# nola2.net
KiCad netlist of a schematic drawn in EAGLE
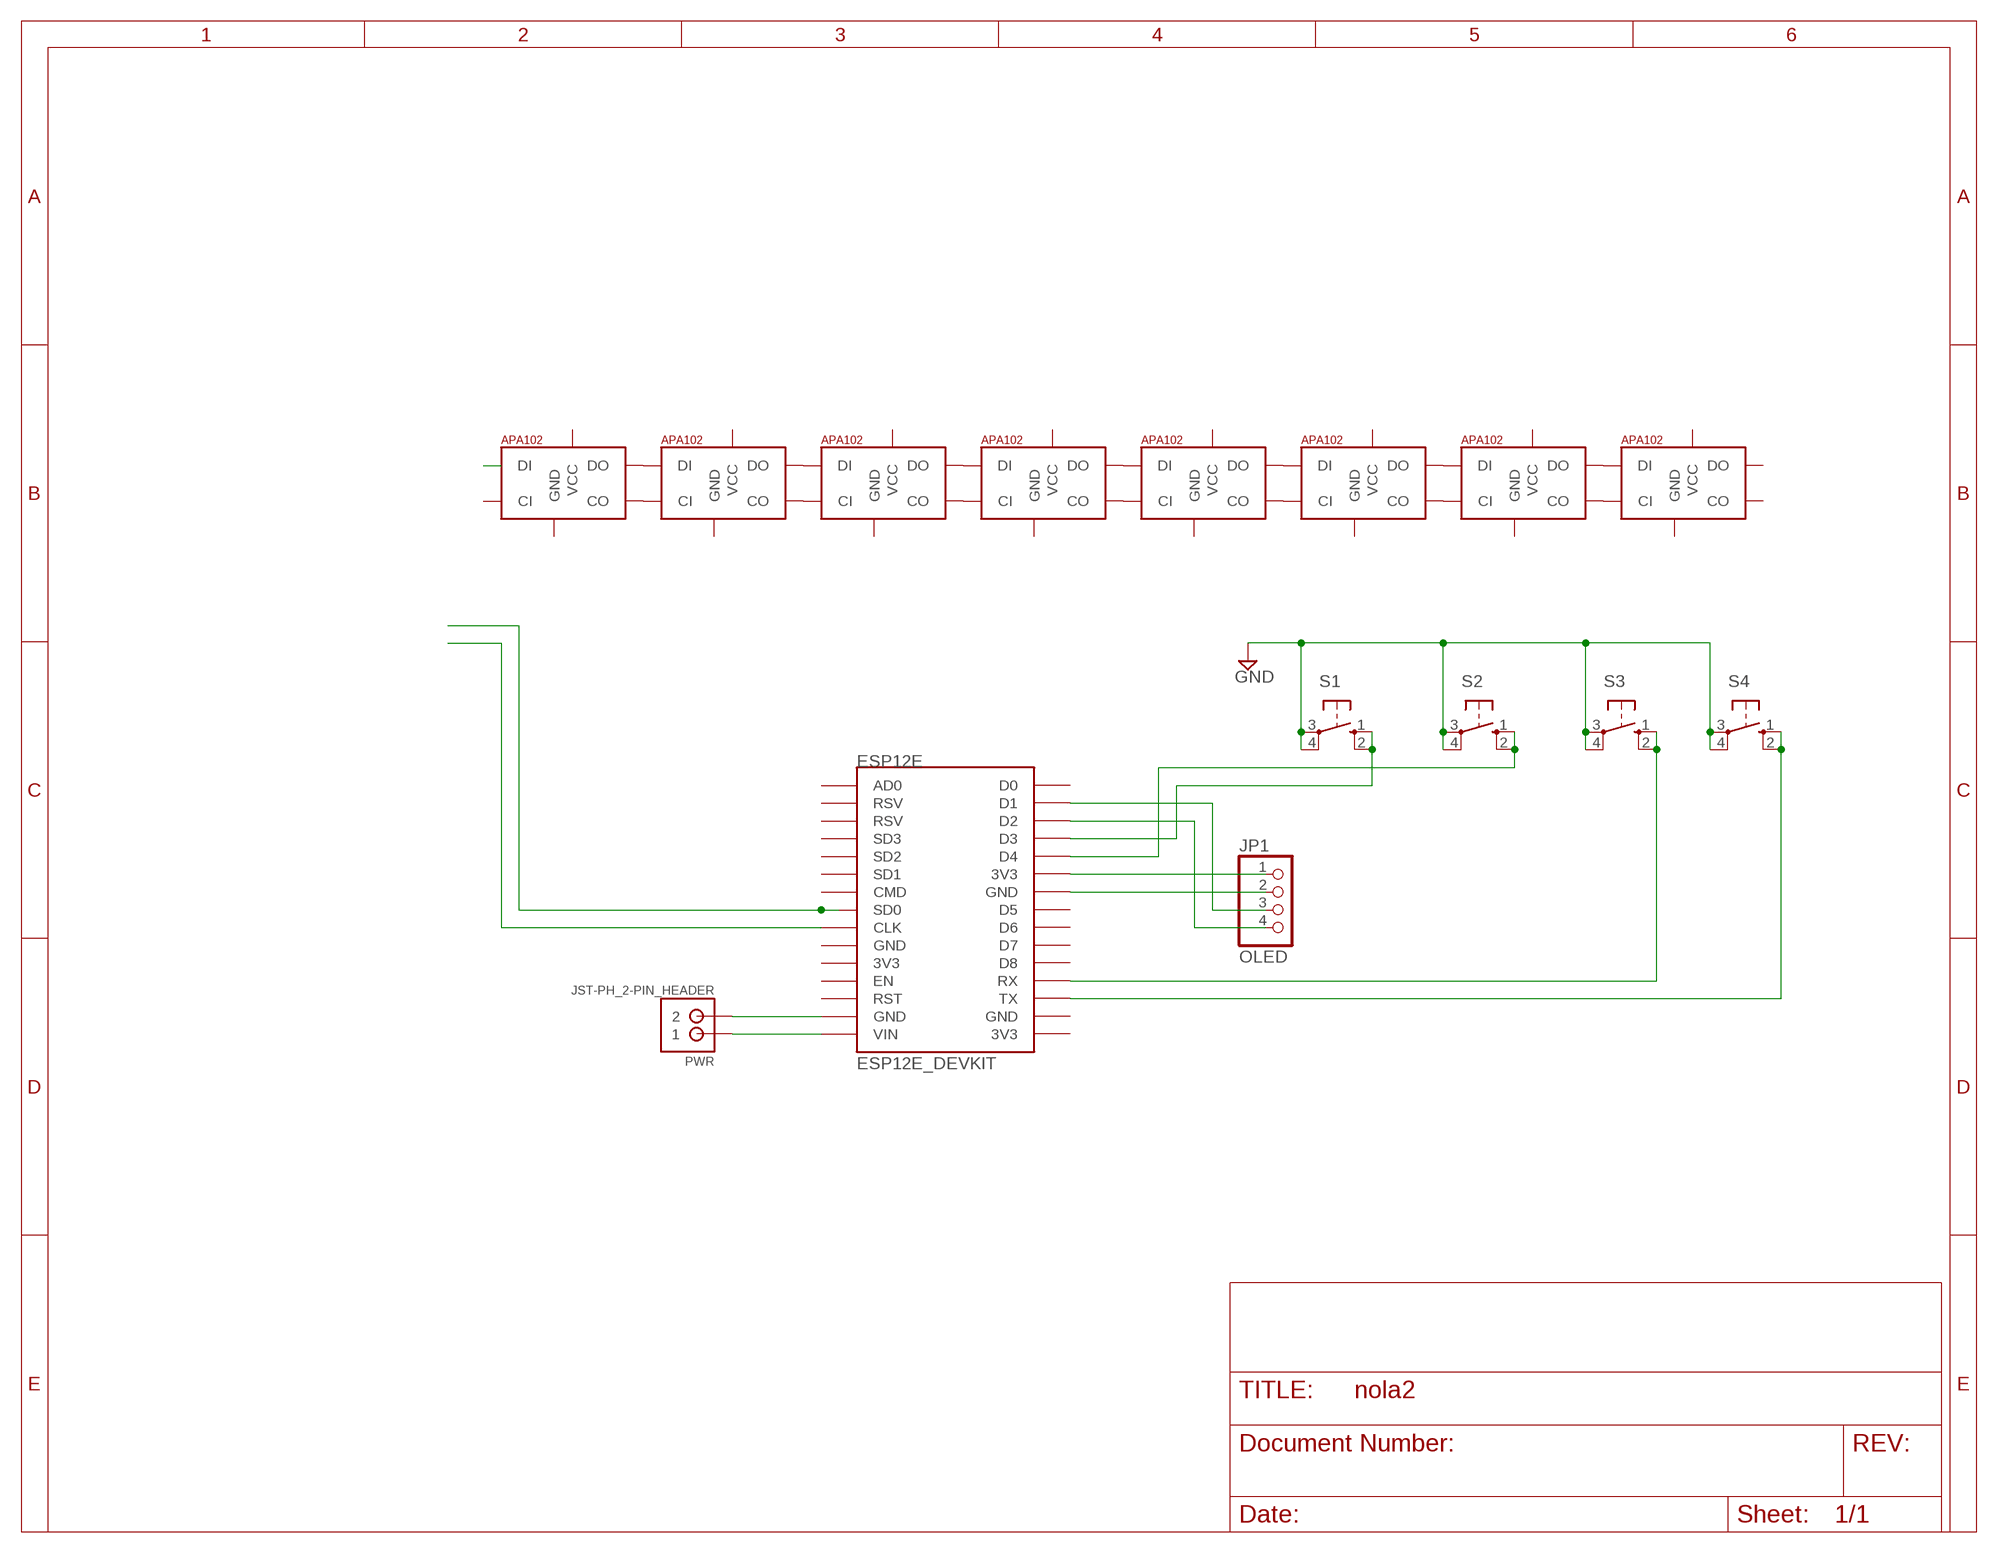
[diagram p0: schematic, sheet 1]

(export (version "E")
  (design (tool "Eeschema 10.0.6"))
  (components
    (comp (ref "ESP12E")
      (value "ESP12E_DEVKIT")
      (footprint "eagle-import:ESP12E_DEVKIT")
      (libsource (lib "eagle-import") (part "ESP12E_DEVKIT"))
    )
    (comp (ref "JP1")
      (value "OLED")
      (footprint "eagle-import:1X04")
      (libsource (lib "eagle-import") (part "PINHD-1X4"))
    )
    (comp (ref "LED1")
      (value "APA1025050")
      (footprint "eagle-import:APA102_5050")
      (libsource (lib "eagle-import") (part "APA1025050"))
    )
    (comp (ref "LED2")
      (value "APA1025050")
      (footprint "eagle-import:APA102_5050")
      (libsource (lib "eagle-import") (part "APA1025050"))
    )
    (comp (ref "LED3")
      (value "APA1025050")
      (footprint "eagle-import:APA102_5050")
      (libsource (lib "eagle-import") (part "APA1025050"))
    )
    (comp (ref "LED4")
      (value "APA1025050")
      (footprint "eagle-import:APA102_5050")
      (libsource (lib "eagle-import") (part "APA1025050"))
    )
    (comp (ref "LED5")
      (value "APA1025050")
      (footprint "eagle-import:APA102_5050")
      (libsource (lib "eagle-import") (part "APA1025050"))
    )
    (comp (ref "LED6")
      (value "APA1025050")
      (footprint "eagle-import:APA102_5050")
      (libsource (lib "eagle-import") (part "APA1025050"))
    )
    (comp (ref "LED7")
      (value "APA1025050")
      (footprint "eagle-import:APA102_5050")
      (libsource (lib "eagle-import") (part "APA1025050"))
    )
    (comp (ref "LED8")
      (value "APA1025050")
      (footprint "eagle-import:APA102_5050")
      (libsource (lib "eagle-import") (part "APA1025050"))
    )
    (comp (ref "PWR")
      (value "JST-PH_2-PIN_HEADER")
      (footprint "eagle-import:JST_B2B-PH_HEADER")
      (libsource (lib "eagle-import") (part "JST-PH_2-PIN_HEADER"))
    )
    (comp (ref "S1")
      (value "10-XX")
      (footprint "eagle-import:B3F-10XX")
      (fields (field (name "MPN") "B3F-1000"))
      (libsource (lib "eagle-import") (part "10-XX"))
    )
    (comp (ref "S2")
      (value "10-XX")
      (footprint "eagle-import:B3F-10XX")
      (fields (field (name "MPN") "B3F-1000"))
      (libsource (lib "eagle-import") (part "10-XX"))
    )
    (comp (ref "S3")
      (value "10-XX")
      (footprint "eagle-import:B3F-10XX")
      (fields (field (name "MPN") "B3F-1000"))
      (libsource (lib "eagle-import") (part "10-XX"))
    )
    (comp (ref "S4")
      (value "10-XX")
      (footprint "eagle-import:B3F-10XX")
      (fields (field (name "MPN") "B3F-1000"))
      (libsource (lib "eagle-import") (part "10-XX"))
    )
  )
  (nets
    (net (code "1") (name "GND") (class "Default")
      (node (ref "S1") (pin "3") (pinfunction "P_3") (pintype "passive"))
      (node (ref "S1") (pin "4") (pinfunction "P1_4") (pintype "passive"))
      (node (ref "S2") (pin "3") (pinfunction "P_3") (pintype "passive"))
      (node (ref "S2") (pin "4") (pinfunction "P1_4") (pintype "passive"))
      (node (ref "S3") (pin "3") (pinfunction "P_3") (pintype "passive"))
      (node (ref "S3") (pin "4") (pinfunction "P1_4") (pintype "passive"))
      (node (ref "S4") (pin "3") (pinfunction "P_3") (pintype "passive"))
      (node (ref "S4") (pin "4") (pinfunction "P1_4") (pintype "passive"))
    )
    (net (code "2") (name "Net-(ESP12E-3V3-Pad3V3@1)") (class "Default")
      (node (ref "ESP12E") (pin "3V3@1") (pinfunction "3V3_3V3@1") (pintype "bidirectional"))
      (node (ref "JP1") (pin "1") (pinfunction "1_1") (pintype "passive"))
    )
    (net (code "3") (name "Net-(ESP12E-GND-PadGND@2)") (class "Default")
      (node (ref "ESP12E") (pin "GND@2") (pinfunction "GND_GND@2") (pintype "bidirectional"))
      (node (ref "JP1") (pin "2") (pinfunction "2_2") (pintype "passive"))
    )
    (net (code "4") (name "Net-(ESP12E-PadD1)") (class "Default")
      (node (ref "ESP12E") (pin "D1") (pinfunction "D1_D1") (pintype "bidirectional"))
      (node (ref "JP1") (pin "3") (pinfunction "3_3") (pintype "passive"))
    )
    (net (code "5") (name "Net-(ESP12E-PadD2)") (class "Default")
      (node (ref "ESP12E") (pin "D2") (pinfunction "D2_D2") (pintype "bidirectional"))
      (node (ref "JP1") (pin "4") (pinfunction "4_4") (pintype "passive"))
    )
    (net (code "6") (name "Net-(LED1-CO)") (class "Default")
      (node (ref "LED1") (pin "2") (pinfunction "CO_2") (pintype "bidirectional"))
      (node (ref "LED2") (pin "5") (pinfunction "CI_5") (pintype "bidirectional"))
    )
    (net (code "7") (name "Net-(LED1-DO)") (class "Default")
      (node (ref "LED1") (pin "3") (pinfunction "DO_3") (pintype "bidirectional"))
      (node (ref "LED2") (pin "4") (pinfunction "DI_4") (pintype "bidirectional"))
    )
    (net (code "8") (name "Net-(LED2-CO)") (class "Default")
      (node (ref "LED2") (pin "2") (pinfunction "CO_2") (pintype "bidirectional"))
      (node (ref "LED3") (pin "5") (pinfunction "CI_5") (pintype "bidirectional"))
    )
    (net (code "9") (name "Net-(LED2-DO)") (class "Default")
      (node (ref "LED2") (pin "3") (pinfunction "DO_3") (pintype "bidirectional"))
      (node (ref "LED3") (pin "4") (pinfunction "DI_4") (pintype "bidirectional"))
    )
    (net (code "10") (name "Net-(LED3-CO)") (class "Default")
      (node (ref "LED3") (pin "2") (pinfunction "CO_2") (pintype "bidirectional"))
      (node (ref "LED4") (pin "5") (pinfunction "CI_5") (pintype "bidirectional"))
    )
    (net (code "11") (name "Net-(LED3-DO)") (class "Default")
      (node (ref "LED3") (pin "3") (pinfunction "DO_3") (pintype "bidirectional"))
      (node (ref "LED4") (pin "4") (pinfunction "DI_4") (pintype "bidirectional"))
    )
    (net (code "12") (name "Net-(LED4-CO)") (class "Default")
      (node (ref "LED4") (pin "2") (pinfunction "CO_2") (pintype "bidirectional"))
      (node (ref "LED5") (pin "5") (pinfunction "CI_5") (pintype "bidirectional"))
    )
    (net (code "13") (name "Net-(LED4-DO)") (class "Default")
      (node (ref "LED4") (pin "3") (pinfunction "DO_3") (pintype "bidirectional"))
      (node (ref "LED5") (pin "4") (pinfunction "DI_4") (pintype "bidirectional"))
    )
    (net (code "14") (name "Net-(LED5-CO)") (class "Default")
      (node (ref "LED5") (pin "2") (pinfunction "CO_2") (pintype "bidirectional"))
      (node (ref "LED6") (pin "5") (pinfunction "CI_5") (pintype "bidirectional"))
    )
    (net (code "15") (name "Net-(LED5-DO)") (class "Default")
      (node (ref "LED5") (pin "3") (pinfunction "DO_3") (pintype "bidirectional"))
      (node (ref "LED6") (pin "4") (pinfunction "DI_4") (pintype "bidirectional"))
    )
    (net (code "16") (name "Net-(LED6-CO)") (class "Default")
      (node (ref "LED6") (pin "2") (pinfunction "CO_2") (pintype "bidirectional"))
      (node (ref "LED7") (pin "5") (pinfunction "CI_5") (pintype "bidirectional"))
    )
    (net (code "17") (name "Net-(LED6-DO)") (class "Default")
      (node (ref "LED6") (pin "3") (pinfunction "DO_3") (pintype "bidirectional"))
      (node (ref "LED7") (pin "4") (pinfunction "DI_4") (pintype "bidirectional"))
    )
    (net (code "18") (name "Net-(LED7-CO)") (class "Default")
      (node (ref "LED7") (pin "2") (pinfunction "CO_2") (pintype "bidirectional"))
      (node (ref "LED8") (pin "5") (pinfunction "CI_5") (pintype "bidirectional"))
    )
    (net (code "19") (name "Net-(LED7-DO)") (class "Default")
      (node (ref "LED7") (pin "3") (pinfunction "DO_3") (pintype "bidirectional"))
      (node (ref "LED8") (pin "4") (pinfunction "DI_4") (pintype "bidirectional"))
    )
    (net (code "20") (name "Net-(PWR-1)") (class "Default")
      (node (ref "ESP12E") (pin "VIN") (pinfunction "VIN_VIN") (pintype "bidirectional"))
      (node (ref "PWR") (pin "P1") (pinfunction "1_P1") (pintype "bidirectional"))
    )
    (net (code "21") (name "Net-(PWR-2)") (class "Default")
      (node (ref "ESP12E") (pin "GND@1") (pinfunction "GND_GND@1") (pintype "bidirectional"))
      (node (ref "PWR") (pin "P2") (pinfunction "2_P2") (pintype "bidirectional"))
    )
    (net (code "22") (name "Net-(S1-S)") (class "Default")
      (node (ref "ESP12E") (pin "D3") (pinfunction "D3_D3") (pintype "bidirectional"))
      (node (ref "S1") (pin "1") (pinfunction "S_1") (pintype "passive"))
      (node (ref "S1") (pin "2") (pinfunction "S1_2") (pintype "passive"))
    )
    (net (code "23") (name "Net-(S2-S)") (class "Default")
      (node (ref "ESP12E") (pin "D4") (pinfunction "D4_D4") (pintype "bidirectional"))
      (node (ref "S2") (pin "1") (pinfunction "S_1") (pintype "passive"))
      (node (ref "S2") (pin "2") (pinfunction "S1_2") (pintype "passive"))
    )
    (net (code "24") (name "Net-(S3-S)") (class "Default")
      (node (ref "ESP12E") (pin "RX") (pinfunction "RX_RX") (pintype "bidirectional"))
      (node (ref "S3") (pin "1") (pinfunction "S_1") (pintype "passive"))
      (node (ref "S3") (pin "2") (pinfunction "S1_2") (pintype "passive"))
    )
    (net (code "25") (name "Net-(S4-S)") (class "Default")
      (node (ref "ESP12E") (pin "TX") (pinfunction "TX_TX") (pintype "bidirectional"))
      (node (ref "S4") (pin "1") (pinfunction "S_1") (pintype "passive"))
      (node (ref "S4") (pin "2") (pinfunction "S1_2") (pintype "passive"))
    )
    (net (code "26") (name "unconnected-(ESP12E-3V3-Pad3V3@0)") (class "Default")
      (node (ref "ESP12E") (pin "3V3@0") (pinfunction "3V3_3V3@0") (pintype "bidirectional"))
    )
    (net (code "27") (name "unconnected-(ESP12E-3V3-Pad3V3@2)") (class "Default")
      (node (ref "ESP12E") (pin "3V3@2") (pinfunction "3V3_3V3@2") (pintype "bidirectional"))
    )
    (net (code "28") (name "unconnected-(ESP12E-GND-PadGND@0)") (class "Default")
      (node (ref "ESP12E") (pin "GND@0") (pinfunction "GND_GND@0") (pintype "bidirectional"))
    )
    (net (code "29") (name "unconnected-(ESP12E-GND-PadGND@3)") (class "Default")
      (node (ref "ESP12E") (pin "GND@3") (pinfunction "GND_GND@3") (pintype "bidirectional"))
    )
    (net (code "30") (name "unconnected-(ESP12E-PadAD0)") (class "Default")
      (node (ref "ESP12E") (pin "AD0") (pinfunction "AD0_AD0") (pintype "bidirectional"))
    )
    (net (code "31") (name "unconnected-(ESP12E-PadCLK)") (class "Default")
      (node (ref "ESP12E") (pin "CLK") (pinfunction "CLK_CLK") (pintype "bidirectional"))
    )
    (net (code "32") (name "unconnected-(ESP12E-PadCMD)") (class "Default")
      (node (ref "ESP12E") (pin "CMD") (pinfunction "CMD_CMD") (pintype "bidirectional"))
    )
    (net (code "33") (name "unconnected-(ESP12E-PadD0)") (class "Default")
      (node (ref "ESP12E") (pin "D0") (pinfunction "D0_D0") (pintype "bidirectional"))
    )
    (net (code "34") (name "unconnected-(ESP12E-PadD5)") (class "Default")
      (node (ref "ESP12E") (pin "D5") (pinfunction "D5_D5") (pintype "bidirectional"))
    )
    (net (code "35") (name "unconnected-(ESP12E-PadD6)") (class "Default")
      (node (ref "ESP12E") (pin "D6") (pinfunction "D6_D6") (pintype "bidirectional"))
    )
    (net (code "36") (name "unconnected-(ESP12E-PadD7)") (class "Default")
      (node (ref "ESP12E") (pin "D7") (pinfunction "D7_D7") (pintype "bidirectional"))
    )
    (net (code "37") (name "unconnected-(ESP12E-PadD8)") (class "Default")
      (node (ref "ESP12E") (pin "D8") (pinfunction "D8_D8") (pintype "bidirectional"))
    )
    (net (code "38") (name "unconnected-(ESP12E-PadEN)") (class "Default")
      (node (ref "ESP12E") (pin "EN") (pinfunction "EN_EN") (pintype "bidirectional"))
    )
    (net (code "39") (name "unconnected-(ESP12E-PadRST)") (class "Default")
      (node (ref "ESP12E") (pin "RST") (pinfunction "RST_RST") (pintype "bidirectional"))
    )
    (net (code "40") (name "unconnected-(ESP12E-PadSD0)") (class "Default")
      (node (ref "ESP12E") (pin "SD0") (pinfunction "SD0_SD0") (pintype "bidirectional"))
    )
    (net (code "41") (name "unconnected-(ESP12E-PadSD1)") (class "Default")
      (node (ref "ESP12E") (pin "SD1") (pinfunction "SD1_SD1") (pintype "bidirectional"))
    )
    (net (code "42") (name "unconnected-(ESP12E-PadSD2)") (class "Default")
      (node (ref "ESP12E") (pin "SD2") (pinfunction "SD2_SD2") (pintype "bidirectional"))
    )
    (net (code "43") (name "unconnected-(ESP12E-PadSD3)") (class "Default")
      (node (ref "ESP12E") (pin "SD3") (pinfunction "SD3_SD3") (pintype "bidirectional"))
    )
    (net (code "44") (name "unconnected-(ESP12E-RSV-PadRSV@0)") (class "Default")
      (node (ref "ESP12E") (pin "RSV@0") (pinfunction "RSV_RSV@0") (pintype "bidirectional"))
    )
    (net (code "45") (name "unconnected-(ESP12E-RSV-PadRSV@1)") (class "Default")
      (node (ref "ESP12E") (pin "RSV@1") (pinfunction "RSV_RSV@1") (pintype "bidirectional"))
    )
    (net (code "46") (name "unconnected-(LED1-CI-Pad5)") (class "Default")
      (node (ref "LED1") (pin "5") (pinfunction "CI_5") (pintype "bidirectional"))
    )
    (net (code "47") (name "unconnected-(LED1-DI-Pad4)") (class "Default")
      (node (ref "LED1") (pin "4") (pinfunction "DI_4") (pintype "bidirectional"))
    )
    (net (code "48") (name "unconnected-(LED1-GND-Pad6)") (class "Default")
      (node (ref "LED1") (pin "6") (pinfunction "GND_6") (pintype "bidirectional"))
    )
    (net (code "49") (name "unconnected-(LED1-VCC-Pad1)") (class "Default")
      (node (ref "LED1") (pin "1") (pinfunction "VCC_1") (pintype "bidirectional"))
    )
    (net (code "50") (name "unconnected-(LED2-GND-Pad6)") (class "Default")
      (node (ref "LED2") (pin "6") (pinfunction "GND_6") (pintype "bidirectional"))
    )
    (net (code "51") (name "unconnected-(LED2-VCC-Pad1)") (class "Default")
      (node (ref "LED2") (pin "1") (pinfunction "VCC_1") (pintype "bidirectional"))
    )
    (net (code "52") (name "unconnected-(LED3-GND-Pad6)") (class "Default")
      (node (ref "LED3") (pin "6") (pinfunction "GND_6") (pintype "bidirectional"))
    )
    (net (code "53") (name "unconnected-(LED3-VCC-Pad1)") (class "Default")
      (node (ref "LED3") (pin "1") (pinfunction "VCC_1") (pintype "bidirectional"))
    )
    (net (code "54") (name "unconnected-(LED4-GND-Pad6)") (class "Default")
      (node (ref "LED4") (pin "6") (pinfunction "GND_6") (pintype "bidirectional"))
    )
    (net (code "55") (name "unconnected-(LED4-VCC-Pad1)") (class "Default")
      (node (ref "LED4") (pin "1") (pinfunction "VCC_1") (pintype "bidirectional"))
    )
    (net (code "56") (name "unconnected-(LED5-GND-Pad6)") (class "Default")
      (node (ref "LED5") (pin "6") (pinfunction "GND_6") (pintype "bidirectional"))
    )
    (net (code "57") (name "unconnected-(LED5-VCC-Pad1)") (class "Default")
      (node (ref "LED5") (pin "1") (pinfunction "VCC_1") (pintype "bidirectional"))
    )
    (net (code "58") (name "unconnected-(LED6-GND-Pad6)") (class "Default")
      (node (ref "LED6") (pin "6") (pinfunction "GND_6") (pintype "bidirectional"))
    )
    (net (code "59") (name "unconnected-(LED6-VCC-Pad1)") (class "Default")
      (node (ref "LED6") (pin "1") (pinfunction "VCC_1") (pintype "bidirectional"))
    )
    (net (code "60") (name "unconnected-(LED7-GND-Pad6)") (class "Default")
      (node (ref "LED7") (pin "6") (pinfunction "GND_6") (pintype "bidirectional"))
    )
    (net (code "61") (name "unconnected-(LED7-VCC-Pad1)") (class "Default")
      (node (ref "LED7") (pin "1") (pinfunction "VCC_1") (pintype "bidirectional"))
    )
    (net (code "62") (name "unconnected-(LED8-CO-Pad2)") (class "Default")
      (node (ref "LED8") (pin "2") (pinfunction "CO_2") (pintype "bidirectional"))
    )
    (net (code "63") (name "unconnected-(LED8-DO-Pad3)") (class "Default")
      (node (ref "LED8") (pin "3") (pinfunction "DO_3") (pintype "bidirectional"))
    )
    (net (code "64") (name "unconnected-(LED8-GND-Pad6)") (class "Default")
      (node (ref "LED8") (pin "6") (pinfunction "GND_6") (pintype "bidirectional"))
    )
    (net (code "65") (name "unconnected-(LED8-VCC-Pad1)") (class "Default")
      (node (ref "LED8") (pin "1") (pinfunction "VCC_1") (pintype "bidirectional"))
    )
  )
)
